# Application_Board.net
KiCad netlist of a schematic drawn in EAGLE
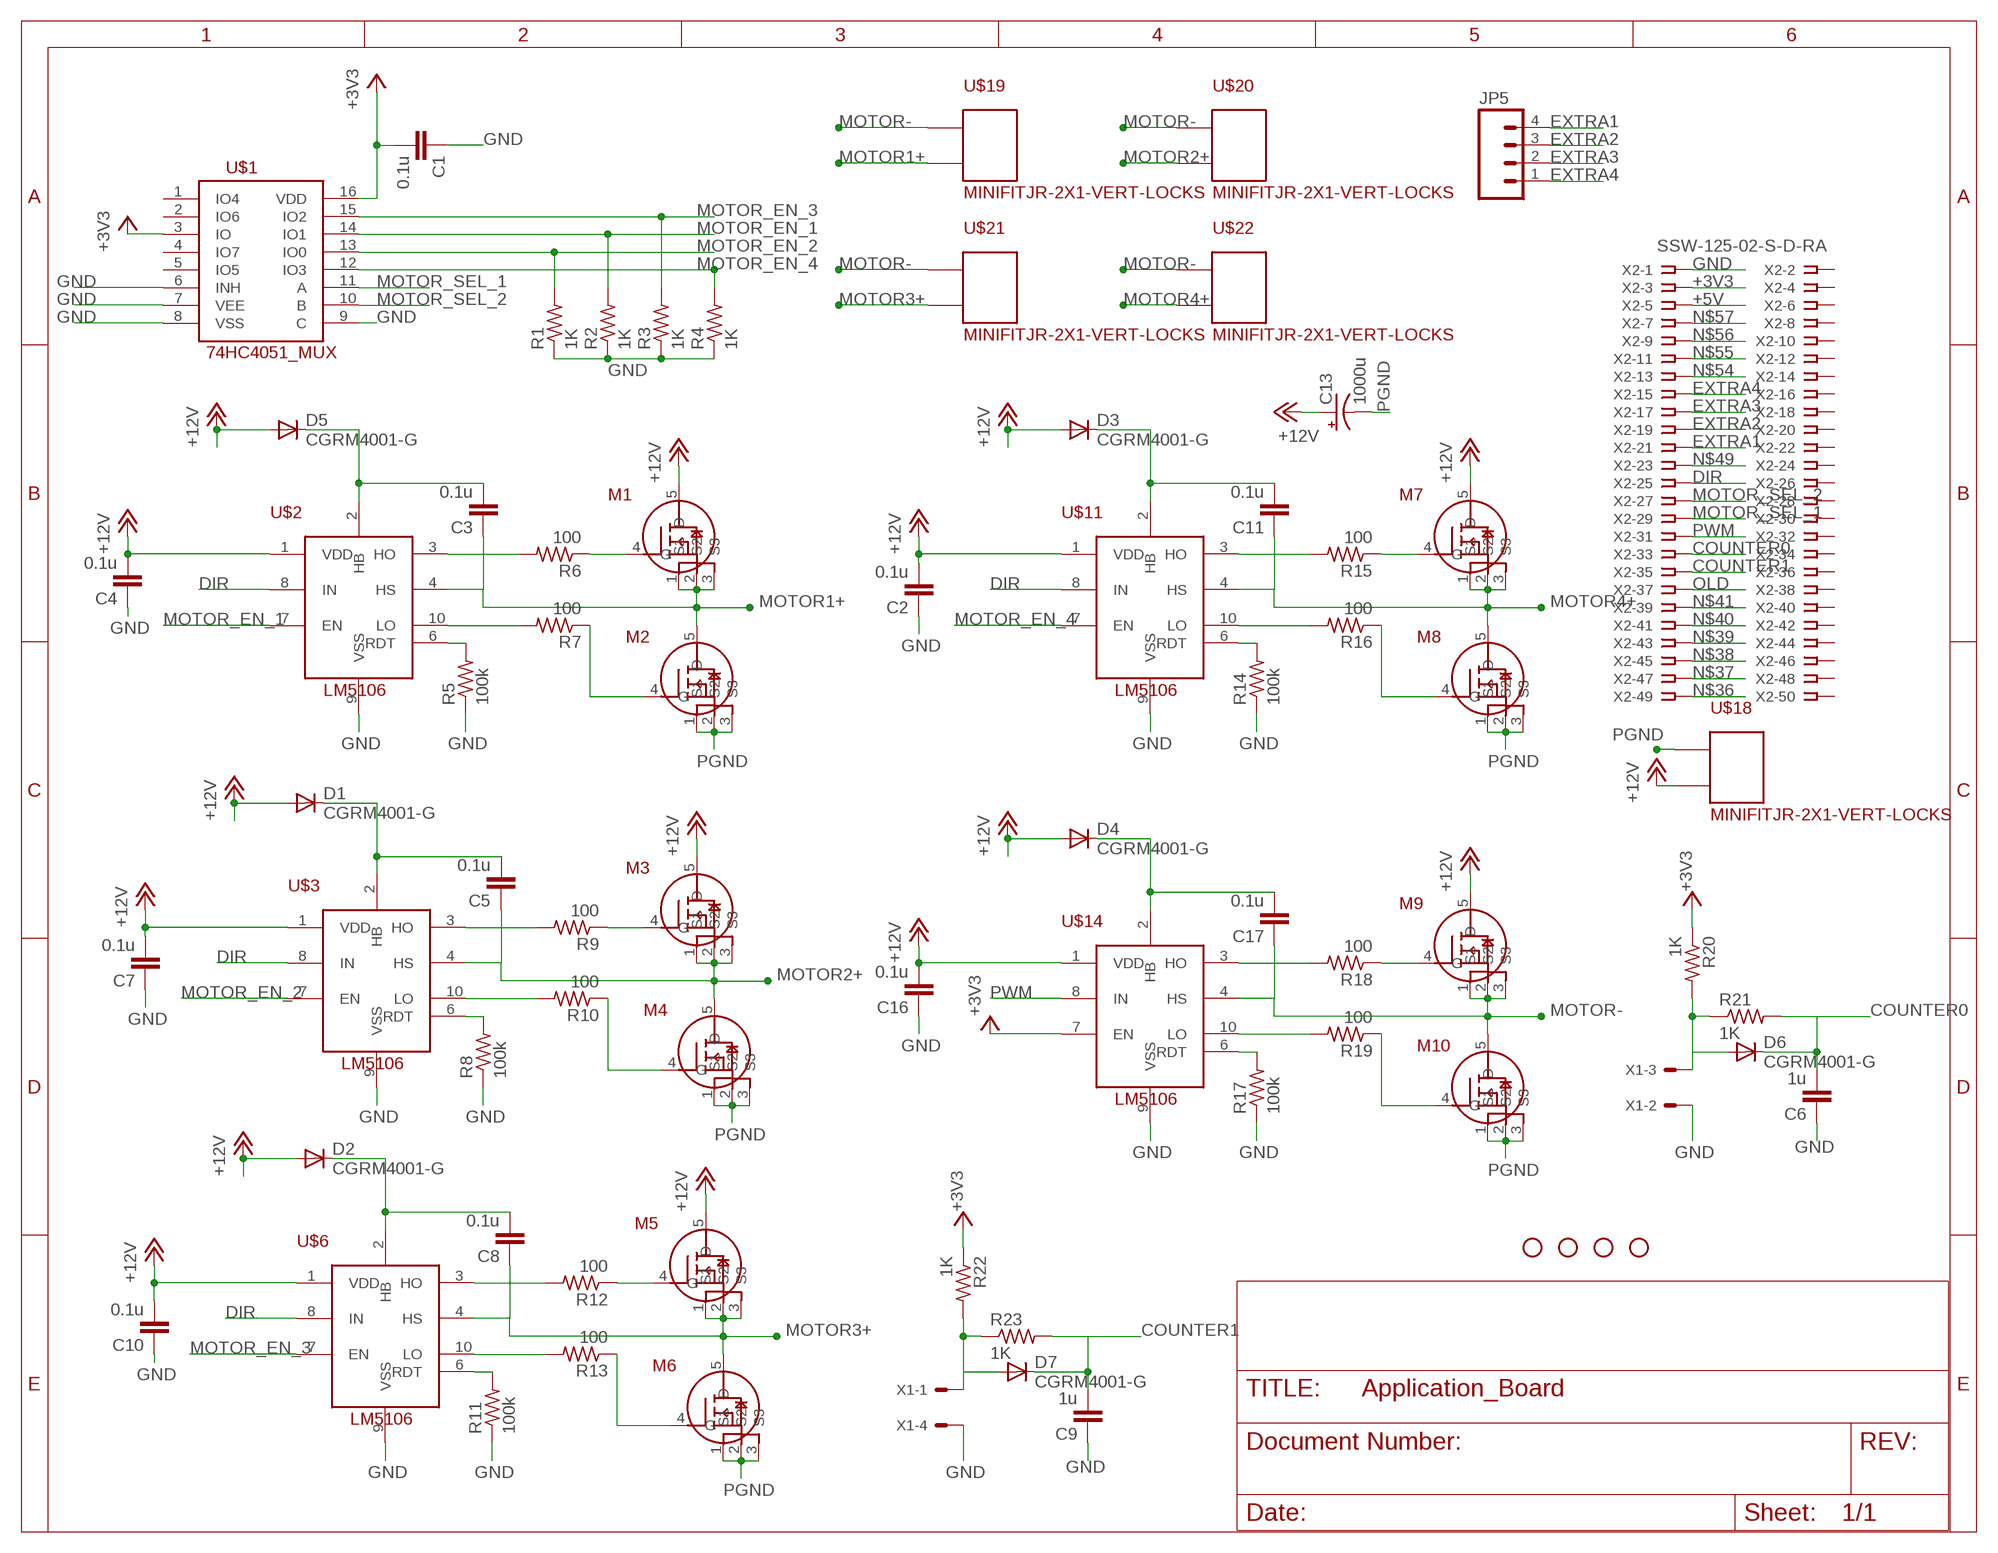
[diagram p0: schematic, sheet 1]

(export (version "E")
  (design (tool "Eeschema 10.0.6"))
  (components
    (comp (ref "C1")
      (value "0.1u")
      (footprint "eagle-import:0805")
      (libsource (lib "eagle-import") (part "CAP0805"))
    )
    (comp (ref "C2")
      (value "0.1u")
      (footprint "eagle-import:0805")
      (libsource (lib "eagle-import") (part "CAP0805"))
    )
    (comp (ref "C3")
      (value "0.1u")
      (footprint "eagle-import:0805")
      (libsource (lib "eagle-import") (part "CAP0805"))
    )
    (comp (ref "C4")
      (value "0.1u")
      (footprint "eagle-import:0805")
      (libsource (lib "eagle-import") (part "CAP0805"))
    )
    (comp (ref "C5")
      (value "0.1u")
      (footprint "eagle-import:0805")
      (libsource (lib "eagle-import") (part "CAP0805"))
    )
    (comp (ref "C6")
      (value "1u")
      (footprint "eagle-import:0805")
      (libsource (lib "eagle-import") (part "CAP0805"))
    )
    (comp (ref "C7")
      (value "0.1u")
      (footprint "eagle-import:0805")
      (libsource (lib "eagle-import") (part "CAP0805"))
    )
    (comp (ref "C8")
      (value "0.1u")
      (footprint "eagle-import:0805")
      (libsource (lib "eagle-import") (part "CAP0805"))
    )
    (comp (ref "C9")
      (value "1u")
      (footprint "eagle-import:0805")
      (libsource (lib "eagle-import") (part "CAP0805"))
    )
    (comp (ref "C10")
      (value "0.1u")
      (footprint "eagle-import:0805")
      (libsource (lib "eagle-import") (part "CAP0805"))
    )
    (comp (ref "C11")
      (value "0.1u")
      (footprint "eagle-import:0805")
      (libsource (lib "eagle-import") (part "CAP0805"))
    )
    (comp (ref "C13")
      (value "1000u")
      (footprint "eagle-import:UD-18X19,1_NICHICON")
      (libsource (lib "eagle-import") (part "CPOL-US"))
    )
    (comp (ref "C16")
      (value "0.1u")
      (footprint "eagle-import:0805")
      (libsource (lib "eagle-import") (part "CAP0805"))
    )
    (comp (ref "C17")
      (value "0.1u")
      (footprint "eagle-import:0805")
      (libsource (lib "eagle-import") (part "CAP0805"))
    )
    (comp (ref "D1")
      (value "CGRM4001-G")
      (footprint "eagle-import:SOD-123_MINI-SMA")
      (libsource (lib "eagle-import") (part "CGRM400-G1"))
    )
    (comp (ref "D2")
      (value "CGRM4001-G")
      (footprint "eagle-import:SOD-123_MINI-SMA")
      (libsource (lib "eagle-import") (part "CGRM400-G1"))
    )
    (comp (ref "D3")
      (value "CGRM4001-G")
      (footprint "eagle-import:SOD-123_MINI-SMA")
      (libsource (lib "eagle-import") (part "CGRM400-G1"))
    )
    (comp (ref "D4")
      (value "CGRM4001-G")
      (footprint "eagle-import:SOD-123_MINI-SMA")
      (libsource (lib "eagle-import") (part "CGRM400-G1"))
    )
    (comp (ref "D5")
      (value "CGRM4001-G")
      (footprint "eagle-import:SOD-123_MINI-SMA")
      (libsource (lib "eagle-import") (part "CGRM400-G1"))
    )
    (comp (ref "D6")
      (value "CGRM4001-G")
      (footprint "eagle-import:SOD-123_MINI-SMA")
      (libsource (lib "eagle-import") (part "CGRM400-G1"))
    )
    (comp (ref "D7")
      (value "CGRM4001-G")
      (footprint "eagle-import:SOD-123_MINI-SMA")
      (libsource (lib "eagle-import") (part "CGRM400-G1"))
    )
    (comp (ref "JP1")
      (value "STAND-OFF")
      (footprint "eagle-import:STAND-OFF")
      (libsource (lib "eagle-import") (part "STAND-OFF"))
    )
    (comp (ref "JP2")
      (value "STAND-OFF")
      (footprint "eagle-import:STAND-OFF")
      (libsource (lib "eagle-import") (part "STAND-OFF"))
    )
    (comp (ref "JP3")
      (value "STAND-OFF")
      (footprint "eagle-import:STAND-OFF")
      (libsource (lib "eagle-import") (part "STAND-OFF"))
    )
    (comp (ref "JP4")
      (value "STAND-OFF")
      (footprint "eagle-import:STAND-OFF")
      (libsource (lib "eagle-import") (part "STAND-OFF"))
    )
    (comp (ref "JP5")
      (value "M041X04_NO_SILK")
      (footprint "eagle-import:1X04_NO_SILK")
      (libsource (lib "eagle-import") (part "M041X04_NO_SILK"))
    )
    (comp (ref "M1")
      (value "M")
      (footprint "eagle-import:TO127P600X120-5N")
      (libsource (lib "eagle-import") (part "PSMN2R0-30YL"))
    )
    (comp (ref "M2")
      (value "M")
      (footprint "eagle-import:TO127P600X120-5N")
      (libsource (lib "eagle-import") (part "PSMN2R0-30YL"))
    )
    (comp (ref "M3")
      (value "M")
      (footprint "eagle-import:TO127P600X120-5N")
      (libsource (lib "eagle-import") (part "PSMN2R0-30YL"))
    )
    (comp (ref "M4")
      (value "M")
      (footprint "eagle-import:TO127P600X120-5N")
      (libsource (lib "eagle-import") (part "PSMN2R0-30YL"))
    )
    (comp (ref "M5")
      (value "M")
      (footprint "eagle-import:TO127P600X120-5N")
      (libsource (lib "eagle-import") (part "PSMN2R0-30YL"))
    )
    (comp (ref "M6")
      (value "M")
      (footprint "eagle-import:TO127P600X120-5N")
      (libsource (lib "eagle-import") (part "PSMN2R0-30YL"))
    )
    (comp (ref "M7")
      (value "M")
      (footprint "eagle-import:TO127P600X120-5N")
      (libsource (lib "eagle-import") (part "PSMN2R0-30YL"))
    )
    (comp (ref "M8")
      (value "M")
      (footprint "eagle-import:TO127P600X120-5N")
      (libsource (lib "eagle-import") (part "PSMN2R0-30YL"))
    )
    (comp (ref "M9")
      (value "M")
      (footprint "eagle-import:TO127P600X120-5N")
      (libsource (lib "eagle-import") (part "PSMN2R0-30YL"))
    )
    (comp (ref "M10")
      (value "M")
      (footprint "eagle-import:TO127P600X120-5N")
      (libsource (lib "eagle-import") (part "PSMN2R0-30YL"))
    )
    (comp (ref "R1")
      (value "1K")
      (footprint "eagle-import:R0805")
      (libsource (lib "eagle-import") (part "R-US_R0805"))
    )
    (comp (ref "R2")
      (value "1K")
      (footprint "eagle-import:R0805")
      (libsource (lib "eagle-import") (part "R-US_R0805"))
    )
    (comp (ref "R3")
      (value "1K")
      (footprint "eagle-import:R0805")
      (libsource (lib "eagle-import") (part "R-US_R0805"))
    )
    (comp (ref "R4")
      (value "1K")
      (footprint "eagle-import:R0805")
      (libsource (lib "eagle-import") (part "R-US_R0805"))
    )
    (comp (ref "R5")
      (value "100k")
      (footprint "eagle-import:R0805")
      (libsource (lib "eagle-import") (part "R-US_R0805"))
    )
    (comp (ref "R6")
      (value "100")
      (footprint "eagle-import:R0805")
      (libsource (lib "eagle-import") (part "R-US_R0805"))
    )
    (comp (ref "R7")
      (value "100")
      (footprint "eagle-import:R0805")
      (libsource (lib "eagle-import") (part "R-US_R0805"))
    )
    (comp (ref "R8")
      (value "100k")
      (footprint "eagle-import:R0805")
      (libsource (lib "eagle-import") (part "R-US_R0805"))
    )
    (comp (ref "R9")
      (value "100")
      (footprint "eagle-import:R0805")
      (libsource (lib "eagle-import") (part "R-US_R0805"))
    )
    (comp (ref "R10")
      (value "100")
      (footprint "eagle-import:R0805")
      (libsource (lib "eagle-import") (part "R-US_R0805"))
    )
    (comp (ref "R11")
      (value "100k")
      (footprint "eagle-import:R0805")
      (libsource (lib "eagle-import") (part "R-US_R0805"))
    )
    (comp (ref "R12")
      (value "100")
      (footprint "eagle-import:R0805")
      (libsource (lib "eagle-import") (part "R-US_R0805"))
    )
    (comp (ref "R13")
      (value "100")
      (footprint "eagle-import:R0805")
      (libsource (lib "eagle-import") (part "R-US_R0805"))
    )
    (comp (ref "R14")
      (value "100k")
      (footprint "eagle-import:R0805")
      (libsource (lib "eagle-import") (part "R-US_R0805"))
    )
    (comp (ref "R15")
      (value "100")
      (footprint "eagle-import:R0805")
      (libsource (lib "eagle-import") (part "R-US_R0805"))
    )
    (comp (ref "R16")
      (value "100")
      (footprint "eagle-import:R0805")
      (libsource (lib "eagle-import") (part "R-US_R0805"))
    )
    (comp (ref "R17")
      (value "100k")
      (footprint "eagle-import:R0805")
      (libsource (lib "eagle-import") (part "R-US_R0805"))
    )
    (comp (ref "R18")
      (value "100")
      (footprint "eagle-import:R0805")
      (libsource (lib "eagle-import") (part "R-US_R0805"))
    )
    (comp (ref "R19")
      (value "100")
      (footprint "eagle-import:R0805")
      (libsource (lib "eagle-import") (part "R-US_R0805"))
    )
    (comp (ref "R20")
      (value "1K")
      (footprint "eagle-import:R0805")
      (libsource (lib "eagle-import") (part "R-US_R0805"))
    )
    (comp (ref "R21")
      (value "1K")
      (footprint "eagle-import:R0805")
      (libsource (lib "eagle-import") (part "R-US_R0805"))
    )
    (comp (ref "R22")
      (value "1K")
      (footprint "eagle-import:R0805")
      (libsource (lib "eagle-import") (part "R-US_R0805"))
    )
    (comp (ref "R23")
      (value "1K")
      (footprint "eagle-import:R0805")
      (libsource (lib "eagle-import") (part "R-US_R0805"))
    )
    (comp (ref "U$1")
      (value "74HC4051_MUX")
      (footprint "eagle-import:SO16")
      (libsource (lib "eagle-import") (part "74HC4051_MUX"))
    )
    (comp (ref "U$2")
      (value "LM5106MMSMD-MSOP")
      (footprint "eagle-import:10-MSOP")
      (libsource (lib "eagle-import") (part "LM5106MMSMD-MSOP"))
    )
    (comp (ref "U$3")
      (value "LM5106MMSMD-MSOP")
      (footprint "eagle-import:10-MSOP")
      (libsource (lib "eagle-import") (part "LM5106MMSMD-MSOP"))
    )
    (comp (ref "U$6")
      (value "LM5106MMSMD-MSOP")
      (footprint "eagle-import:10-MSOP")
      (libsource (lib "eagle-import") (part "LM5106MMSMD-MSOP"))
    )
    (comp (ref "U$11")
      (value "LM5106MMSMD-MSOP")
      (footprint "eagle-import:10-MSOP")
      (libsource (lib "eagle-import") (part "LM5106MMSMD-MSOP"))
    )
    (comp (ref "U$14")
      (value "LM5106MMSMD-MSOP")
      (footprint "eagle-import:10-MSOP")
      (libsource (lib "eagle-import") (part "LM5106MMSMD-MSOP"))
    )
    (comp (ref "U$18")
      (value "MINIFITJR-2X1-VERT-LOCKS")
      (footprint "eagle-import:5566-02A2")
      (libsource (lib "eagle-import") (part "MINIFITJR-2X1-VERT-LOCKS"))
    )
    (comp (ref "U$19")
      (value "MINIFITJR-2X1-VERT-LOCKS")
      (footprint "eagle-import:5566-02A2")
      (libsource (lib "eagle-import") (part "MINIFITJR-2X1-VERT-LOCKS"))
    )
    (comp (ref "U$20")
      (value "MINIFITJR-2X1-VERT-LOCKS")
      (footprint "eagle-import:5566-02A2")
      (libsource (lib "eagle-import") (part "MINIFITJR-2X1-VERT-LOCKS"))
    )
    (comp (ref "U$21")
      (value "MINIFITJR-2X1-VERT-LOCKS")
      (footprint "eagle-import:5566-02A2")
      (libsource (lib "eagle-import") (part "MINIFITJR-2X1-VERT-LOCKS"))
    )
    (comp (ref "U$22")
      (value "MINIFITJR-2X1-VERT-LOCKS")
      (footprint "eagle-import:5566-02A2")
      (libsource (lib "eagle-import") (part "MINIFITJR-2X1-VERT-LOCKS"))
    )
    (comp (ref "X1")
      (value "KK-156-4")
      (footprint "eagle-import:KK-156-4")
      (libsource (lib "eagle-import") (part "KK-156-4"))
    )
    (comp (ref "X2")
      (value "SSW-125-02-S-D-RA")
      (footprint "eagle-import:TSW-125-02-S-D-RA")
      (libsource (lib "eagle-import") (part "SSW-125-02-S-D-RA"))
    )
  )
  (nets
    (net (code "1") (name "+3V3") (class "Default")
      (node (ref "C1") (pin "2") (pinfunction "2_2") (pintype "passive"))
      (node (ref "R20") (pin "1") (pinfunction "1_1") (pintype "passive"))
      (node (ref "R22") (pin "1") (pinfunction "1_1") (pintype "passive"))
      (node (ref "U$1") (pin "16") (pinfunction "VDD_16") (pintype "bidirectional"))
      (node (ref "U$1") (pin "3") (pinfunction "IO_3") (pintype "bidirectional"))
      (node (ref "U$14") (pin "7") (pinfunction "EN_7") (pintype "bidirectional"))
      (node (ref "X2") (pin "3") (pinfunction "1_3") (pintype "passive"))
    )
    (net (code "2") (name "+12V") (class "Default")
      (node (ref "C10") (pin "2") (pinfunction "2_2") (pintype "passive"))
      (node (ref "C13") (pin "+") (pinfunction "+_+") (pintype "passive"))
      (node (ref "C16") (pin "2") (pinfunction "2_2") (pintype "passive"))
      (node (ref "C2") (pin "2") (pinfunction "2_2") (pintype "passive"))
      (node (ref "C4") (pin "2") (pinfunction "2_2") (pintype "passive"))
      (node (ref "C7") (pin "2") (pinfunction "2_2") (pintype "passive"))
      (node (ref "D1") (pin "A") (pinfunction "A_A") (pintype "passive"))
      (node (ref "D2") (pin "A") (pinfunction "A_A") (pintype "passive"))
      (node (ref "D3") (pin "A") (pinfunction "A_A") (pintype "passive"))
      (node (ref "D4") (pin "A") (pinfunction "A_A") (pintype "passive"))
      (node (ref "D5") (pin "A") (pinfunction "A_A") (pintype "passive"))
      (node (ref "M1") (pin "5") (pinfunction "D_5") (pintype "bidirectional"))
      (node (ref "M3") (pin "5") (pinfunction "D_5") (pintype "bidirectional"))
      (node (ref "M5") (pin "5") (pinfunction "D_5") (pintype "bidirectional"))
      (node (ref "M7") (pin "5") (pinfunction "D_5") (pintype "bidirectional"))
      (node (ref "M9") (pin "5") (pinfunction "D_5") (pintype "bidirectional"))
      (node (ref "U$11") (pin "1") (pinfunction "VDD_1") (pintype "bidirectional"))
      (node (ref "U$14") (pin "1") (pinfunction "VDD_1") (pintype "bidirectional"))
      (node (ref "U$18") (pin "P$2") (pinfunction "P$2_P$2") (pintype "bidirectional"))
      (node (ref "U$2") (pin "1") (pinfunction "VDD_1") (pintype "bidirectional"))
      (node (ref "U$3") (pin "1") (pinfunction "VDD_1") (pintype "bidirectional"))
      (node (ref "U$6") (pin "1") (pinfunction "VDD_1") (pintype "bidirectional"))
    )
    (net (code "3") (name "/+5V") (class "Default")
      (node (ref "X2") (pin "5") (pinfunction "1_5") (pintype "passive"))
    )
    (net (code "4") (name "/COUNTER0") (class "Default")
      (node (ref "C6") (pin "2") (pinfunction "2_2") (pintype "passive"))
      (node (ref "D6") (pin "C") (pinfunction "C_C") (pintype "passive"))
      (node (ref "R21") (pin "2") (pinfunction "2_2") (pintype "passive"))
      (node (ref "X2") (pin "33") (pinfunction "1_33") (pintype "passive"))
    )
    (net (code "5") (name "/COUNTER1") (class "Default")
      (node (ref "C9") (pin "2") (pinfunction "2_2") (pintype "passive"))
      (node (ref "D7") (pin "C") (pinfunction "C_C") (pintype "passive"))
      (node (ref "R23") (pin "2") (pinfunction "2_2") (pintype "passive"))
      (node (ref "X2") (pin "35") (pinfunction "1_35") (pintype "passive"))
    )
    (net (code "6") (name "/DIR") (class "Default")
      (node (ref "U$11") (pin "8") (pinfunction "IN_8") (pintype "bidirectional"))
      (node (ref "U$2") (pin "8") (pinfunction "IN_8") (pintype "bidirectional"))
      (node (ref "U$3") (pin "8") (pinfunction "IN_8") (pintype "bidirectional"))
      (node (ref "U$6") (pin "8") (pinfunction "IN_8") (pintype "bidirectional"))
      (node (ref "X2") (pin "25") (pinfunction "1_25") (pintype "passive"))
    )
    (net (code "7") (name "/EXTRA1") (class "Default")
      (node (ref "JP5") (pin "4") (pinfunction "4_4") (pintype "passive"))
      (node (ref "X2") (pin "21") (pinfunction "1_21") (pintype "passive"))
    )
    (net (code "8") (name "/EXTRA2") (class "Default")
      (node (ref "JP5") (pin "3") (pinfunction "3_3") (pintype "passive"))
      (node (ref "X2") (pin "19") (pinfunction "1_19") (pintype "passive"))
    )
    (net (code "9") (name "/EXTRA3") (class "Default")
      (node (ref "JP5") (pin "2") (pinfunction "2_2") (pintype "passive"))
      (node (ref "X2") (pin "17") (pinfunction "1_17") (pintype "passive"))
    )
    (net (code "10") (name "/EXTRA4") (class "Default")
      (node (ref "JP5") (pin "1") (pinfunction "1_1") (pintype "passive"))
      (node (ref "X2") (pin "15") (pinfunction "1_15") (pintype "passive"))
    )
    (net (code "11") (name "/GND") (class "Default")
      (node (ref "C1") (pin "1") (pinfunction "1_1") (pintype "passive"))
      (node (ref "C10") (pin "1") (pinfunction "1_1") (pintype "passive"))
      (node (ref "C16") (pin "1") (pinfunction "1_1") (pintype "passive"))
      (node (ref "C2") (pin "1") (pinfunction "1_1") (pintype "passive"))
      (node (ref "C4") (pin "1") (pinfunction "1_1") (pintype "passive"))
      (node (ref "C6") (pin "1") (pinfunction "1_1") (pintype "passive"))
      (node (ref "C7") (pin "1") (pinfunction "1_1") (pintype "passive"))
      (node (ref "C9") (pin "1") (pinfunction "1_1") (pintype "passive"))
      (node (ref "R1") (pin "1") (pinfunction "1_1") (pintype "passive"))
      (node (ref "R11") (pin "1") (pinfunction "1_1") (pintype "passive"))
      (node (ref "R14") (pin "1") (pinfunction "1_1") (pintype "passive"))
      (node (ref "R17") (pin "1") (pinfunction "1_1") (pintype "passive"))
      (node (ref "R2") (pin "1") (pinfunction "1_1") (pintype "passive"))
      (node (ref "R3") (pin "1") (pinfunction "1_1") (pintype "passive"))
      (node (ref "R4") (pin "1") (pinfunction "1_1") (pintype "passive"))
      (node (ref "R5") (pin "1") (pinfunction "1_1") (pintype "passive"))
      (node (ref "R8") (pin "1") (pinfunction "1_1") (pintype "passive"))
      (node (ref "U$1") (pin "6") (pinfunction "INH_6") (pintype "bidirectional"))
      (node (ref "U$1") (pin "7") (pinfunction "VEE_7") (pintype "bidirectional"))
      (node (ref "U$1") (pin "8") (pinfunction "VSS_8") (pintype "bidirectional"))
      (node (ref "U$1") (pin "9") (pinfunction "C_9") (pintype "bidirectional"))
      (node (ref "U$11") (pin "9") (pinfunction "VSS_9") (pintype "bidirectional"))
      (node (ref "U$14") (pin "9") (pinfunction "VSS_9") (pintype "bidirectional"))
      (node (ref "U$2") (pin "9") (pinfunction "VSS_9") (pintype "bidirectional"))
      (node (ref "U$3") (pin "9") (pinfunction "VSS_9") (pintype "bidirectional"))
      (node (ref "U$6") (pin "9") (pinfunction "VSS_9") (pintype "bidirectional"))
      (node (ref "X1") (pin "2") (pinfunction "S_2") (pintype "passive"))
      (node (ref "X1") (pin "4") (pinfunction "S_4") (pintype "passive"))
      (node (ref "X2") (pin "1") (pinfunction "1_1") (pintype "passive"))
    )
    (net (code "12") (name "/MOTOR-") (class "Default")
      (node (ref "C17") (pin "1") (pinfunction "1_1") (pintype "passive"))
      (node (ref "M10") (pin "5") (pinfunction "D_5") (pintype "bidirectional"))
      (node (ref "M9") (pin "1") (pinfunction "S1_1") (pintype "bidirectional"))
      (node (ref "M9") (pin "2") (pinfunction "S2_2") (pintype "bidirectional"))
      (node (ref "M9") (pin "3") (pinfunction "S3_3") (pintype "bidirectional"))
      (node (ref "U$14") (pin "4") (pinfunction "HS_4") (pintype "bidirectional"))
      (node (ref "U$19") (pin "P$1") (pinfunction "P$1_P$1") (pintype "bidirectional"))
      (node (ref "U$20") (pin "P$1") (pinfunction "P$1_P$1") (pintype "bidirectional"))
      (node (ref "U$21") (pin "P$1") (pinfunction "P$1_P$1") (pintype "bidirectional"))
      (node (ref "U$22") (pin "P$1") (pinfunction "P$1_P$1") (pintype "bidirectional"))
    )
    (net (code "13") (name "/MOTOR1+") (class "Default")
      (node (ref "C3") (pin "1") (pinfunction "1_1") (pintype "passive"))
      (node (ref "M1") (pin "1") (pinfunction "S1_1") (pintype "bidirectional"))
      (node (ref "M1") (pin "2") (pinfunction "S2_2") (pintype "bidirectional"))
      (node (ref "M1") (pin "3") (pinfunction "S3_3") (pintype "bidirectional"))
      (node (ref "M2") (pin "5") (pinfunction "D_5") (pintype "bidirectional"))
      (node (ref "U$19") (pin "P$2") (pinfunction "P$2_P$2") (pintype "bidirectional"))
      (node (ref "U$2") (pin "4") (pinfunction "HS_4") (pintype "bidirectional"))
    )
    (net (code "14") (name "/MOTOR2+") (class "Default")
      (node (ref "C5") (pin "1") (pinfunction "1_1") (pintype "passive"))
      (node (ref "M3") (pin "1") (pinfunction "S1_1") (pintype "bidirectional"))
      (node (ref "M3") (pin "2") (pinfunction "S2_2") (pintype "bidirectional"))
      (node (ref "M3") (pin "3") (pinfunction "S3_3") (pintype "bidirectional"))
      (node (ref "M4") (pin "5") (pinfunction "D_5") (pintype "bidirectional"))
      (node (ref "U$20") (pin "P$2") (pinfunction "P$2_P$2") (pintype "bidirectional"))
      (node (ref "U$3") (pin "4") (pinfunction "HS_4") (pintype "bidirectional"))
    )
    (net (code "15") (name "/MOTOR3+") (class "Default")
      (node (ref "C8") (pin "1") (pinfunction "1_1") (pintype "passive"))
      (node (ref "M5") (pin "1") (pinfunction "S1_1") (pintype "bidirectional"))
      (node (ref "M5") (pin "2") (pinfunction "S2_2") (pintype "bidirectional"))
      (node (ref "M5") (pin "3") (pinfunction "S3_3") (pintype "bidirectional"))
      (node (ref "M6") (pin "5") (pinfunction "D_5") (pintype "bidirectional"))
      (node (ref "U$21") (pin "P$2") (pinfunction "P$2_P$2") (pintype "bidirectional"))
      (node (ref "U$6") (pin "4") (pinfunction "HS_4") (pintype "bidirectional"))
    )
    (net (code "16") (name "/MOTOR4+") (class "Default")
      (node (ref "C11") (pin "1") (pinfunction "1_1") (pintype "passive"))
      (node (ref "M7") (pin "1") (pinfunction "S1_1") (pintype "bidirectional"))
      (node (ref "M7") (pin "2") (pinfunction "S2_2") (pintype "bidirectional"))
      (node (ref "M7") (pin "3") (pinfunction "S3_3") (pintype "bidirectional"))
      (node (ref "M8") (pin "5") (pinfunction "D_5") (pintype "bidirectional"))
      (node (ref "U$11") (pin "4") (pinfunction "HS_4") (pintype "bidirectional"))
      (node (ref "U$22") (pin "P$2") (pinfunction "P$2_P$2") (pintype "bidirectional"))
    )
    (net (code "17") (name "/MOTOR_EN_1") (class "Default")
      (node (ref "R2") (pin "2") (pinfunction "2_2") (pintype "passive"))
      (node (ref "U$1") (pin "14") (pinfunction "IO1_14") (pintype "bidirectional"))
      (node (ref "U$2") (pin "7") (pinfunction "EN_7") (pintype "bidirectional"))
    )
    (net (code "18") (name "/MOTOR_EN_2") (class "Default")
      (node (ref "R1") (pin "2") (pinfunction "2_2") (pintype "passive"))
      (node (ref "U$1") (pin "13") (pinfunction "IO0_13") (pintype "bidirectional"))
      (node (ref "U$3") (pin "7") (pinfunction "EN_7") (pintype "bidirectional"))
    )
    (net (code "19") (name "/MOTOR_EN_3") (class "Default")
      (node (ref "R3") (pin "2") (pinfunction "2_2") (pintype "passive"))
      (node (ref "U$1") (pin "15") (pinfunction "IO2_15") (pintype "bidirectional"))
      (node (ref "U$6") (pin "7") (pinfunction "EN_7") (pintype "bidirectional"))
    )
    (net (code "20") (name "/MOTOR_EN_4") (class "Default")
      (node (ref "R4") (pin "2") (pinfunction "2_2") (pintype "passive"))
      (node (ref "U$1") (pin "12") (pinfunction "IO3_12") (pintype "bidirectional"))
      (node (ref "U$11") (pin "7") (pinfunction "EN_7") (pintype "bidirectional"))
    )
    (net (code "21") (name "/MOTOR_SEL_1") (class "Default")
      (node (ref "U$1") (pin "11") (pinfunction "A_11") (pintype "bidirectional"))
      (node (ref "X2") (pin "29") (pinfunction "1_29") (pintype "passive"))
    )
    (net (code "22") (name "/MOTOR_SEL_2") (class "Default")
      (node (ref "U$1") (pin "10") (pinfunction "B_10") (pintype "bidirectional"))
      (node (ref "X2") (pin "27") (pinfunction "1_27") (pintype "passive"))
    )
    (net (code "23") (name "/N$36") (class "Default")
      (node (ref "X2") (pin "49") (pinfunction "1_49") (pintype "passive"))
    )
    (net (code "24") (name "/N$37") (class "Default")
      (node (ref "X2") (pin "47") (pinfunction "1_47") (pintype "passive"))
    )
    (net (code "25") (name "/N$38") (class "Default")
      (node (ref "X2") (pin "45") (pinfunction "1_45") (pintype "passive"))
    )
    (net (code "26") (name "/N$39") (class "Default")
      (node (ref "X2") (pin "43") (pinfunction "1_43") (pintype "passive"))
    )
    (net (code "27") (name "/N$40") (class "Default")
      (node (ref "X2") (pin "41") (pinfunction "1_41") (pintype "passive"))
    )
    (net (code "28") (name "/N$41") (class "Default")
      (node (ref "X2") (pin "39") (pinfunction "1_39") (pintype "passive"))
    )
    (net (code "29") (name "/N$49") (class "Default")
      (node (ref "X2") (pin "23") (pinfunction "1_23") (pintype "passive"))
    )
    (net (code "30") (name "/N$54") (class "Default")
      (node (ref "X2") (pin "13") (pinfunction "1_13") (pintype "passive"))
    )
    (net (code "31") (name "/N$55") (class "Default")
      (node (ref "X2") (pin "11") (pinfunction "1_11") (pintype "passive"))
    )
    (net (code "32") (name "/N$56") (class "Default")
      (node (ref "X2") (pin "9") (pinfunction "1_9") (pintype "passive"))
    )
    (net (code "33") (name "/N$57") (class "Default")
      (node (ref "X2") (pin "7") (pinfunction "1_7") (pintype "passive"))
    )
    (net (code "34") (name "/OLD") (class "Default")
      (node (ref "X2") (pin "37") (pinfunction "1_37") (pintype "passive"))
    )
    (net (code "35") (name "/PGND") (class "Default")
      (node (ref "C13") (pin "-") (pinfunction "-_-") (pintype "passive"))
      (node (ref "M10") (pin "1") (pinfunction "S1_1") (pintype "bidirectional"))
      (node (ref "M10") (pin "2") (pinfunction "S2_2") (pintype "bidirectional"))
      (node (ref "M10") (pin "3") (pinfunction "S3_3") (pintype "bidirectional"))
      (node (ref "M2") (pin "1") (pinfunction "S1_1") (pintype "bidirectional"))
      (node (ref "M2") (pin "2") (pinfunction "S2_2") (pintype "bidirectional"))
      (node (ref "M2") (pin "3") (pinfunction "S3_3") (pintype "bidirectional"))
      (node (ref "M4") (pin "1") (pinfunction "S1_1") (pintype "bidirectional"))
      (node (ref "M4") (pin "2") (pinfunction "S2_2") (pintype "bidirectional"))
      (node (ref "M4") (pin "3") (pinfunction "S3_3") (pintype "bidirectional"))
      (node (ref "M6") (pin "1") (pinfunction "S1_1") (pintype "bidirectional"))
      (node (ref "M6") (pin "2") (pinfunction "S2_2") (pintype "bidirectional"))
      (node (ref "M6") (pin "3") (pinfunction "S3_3") (pintype "bidirectional"))
      (node (ref "M8") (pin "1") (pinfunction "S1_1") (pintype "bidirectional"))
      (node (ref "M8") (pin "2") (pinfunction "S2_2") (pintype "bidirectional"))
      (node (ref "M8") (pin "3") (pinfunction "S3_3") (pintype "bidirectional"))
      (node (ref "U$18") (pin "P$1") (pinfunction "P$1_P$1") (pintype "bidirectional"))
    )
    (net (code "36") (name "/PWM") (class "Default")
      (node (ref "U$14") (pin "8") (pinfunction "IN_8") (pintype "bidirectional"))
      (node (ref "X2") (pin "31") (pinfunction "1_31") (pintype "passive"))
    )
    (net (code "37") (name "Net-(M1-G)") (class "Default")
      (node (ref "M1") (pin "4") (pinfunction "G_4") (pintype "bidirectional"))
      (node (ref "R6") (pin "1") (pinfunction "1_1") (pintype "passive"))
    )
    (net (code "38") (name "Net-(M2-G)") (class "Default")
      (node (ref "M2") (pin "4") (pinfunction "G_4") (pintype "bidirectional"))
      (node (ref "R7") (pin "1") (pinfunction "1_1") (pintype "passive"))
    )
    (net (code "39") (name "Net-(M3-G)") (class "Default")
      (node (ref "M3") (pin "4") (pinfunction "G_4") (pintype "bidirectional"))
      (node (ref "R9") (pin "1") (pinfunction "1_1") (pintype "passive"))
    )
    (net (code "40") (name "Net-(M4-G)") (class "Default")
      (node (ref "M4") (pin "4") (pinfunction "G_4") (pintype "bidirectional"))
      (node (ref "R10") (pin "1") (pinfunction "1_1") (pintype "passive"))
    )
    (net (code "41") (name "Net-(M5-G)") (class "Default")
      (node (ref "M5") (pin "4") (pinfunction "G_4") (pintype "bidirectional"))
      (node (ref "R12") (pin "1") (pinfunction "1_1") (pintype "passive"))
    )
    (net (code "42") (name "Net-(M6-G)") (class "Default")
      (node (ref "M6") (pin "4") (pinfunction "G_4") (pintype "bidirectional"))
      (node (ref "R13") (pin "1") (pinfunction "1_1") (pintype "passive"))
    )
    (net (code "43") (name "Net-(M7-G)") (class "Default")
      (node (ref "M7") (pin "4") (pinfunction "G_4") (pintype "bidirectional"))
      (node (ref "R15") (pin "1") (pinfunction "1_1") (pintype "passive"))
    )
    (net (code "44") (name "Net-(M8-G)") (class "Default")
      (node (ref "M8") (pin "4") (pinfunction "G_4") (pintype "bidirectional"))
      (node (ref "R16") (pin "1") (pinfunction "1_1") (pintype "passive"))
    )
    (net (code "45") (name "Net-(M9-G)") (class "Default")
      (node (ref "M9") (pin "4") (pinfunction "G_4") (pintype "bidirectional"))
      (node (ref "R18") (pin "1") (pinfunction "1_1") (pintype "passive"))
    )
    (net (code "46") (name "Net-(M10-G)") (class "Default")
      (node (ref "M10") (pin "4") (pinfunction "G_4") (pintype "bidirectional"))
      (node (ref "R19") (pin "1") (pinfunction "1_1") (pintype "passive"))
    )
    (net (code "47") (name "Net-(U$2-HB)") (class "Default")
      (node (ref "C3") (pin "2") (pinfunction "2_2") (pintype "passive"))
      (node (ref "D5") (pin "C") (pinfunction "C_C") (pintype "passive"))
      (node (ref "U$2") (pin "2") (pinfunction "HB_2") (pintype "bidirectional"))
    )
    (net (code "48") (name "Net-(U$2-HO)") (class "Default")
      (node (ref "R6") (pin "2") (pinfunction "2_2") (pintype "passive"))
      (node (ref "U$2") (pin "3") (pinfunction "HO_3") (pintype "bidirectional"))
    )
    (net (code "49") (name "Net-(U$2-LO)") (class "Default")
      (node (ref "R7") (pin "2") (pinfunction "2_2") (pintype "passive"))
      (node (ref "U$2") (pin "10") (pinfunction "LO_10") (pintype "bidirectional"))
    )
    (net (code "50") (name "Net-(U$2-RDT)") (class "Default")
      (node (ref "R5") (pin "2") (pinfunction "2_2") (pintype "passive"))
      (node (ref "U$2") (pin "6") (pinfunction "RDT_6") (pintype "bidirectional"))
    )
    (net (code "51") (name "Net-(U$3-HB)") (class "Default")
      (node (ref "C5") (pin "2") (pinfunction "2_2") (pintype "passive"))
      (node (ref "D1") (pin "C") (pinfunction "C_C") (pintype "passive"))
      (node (ref "U$3") (pin "2") (pinfunction "HB_2") (pintype "bidirectional"))
    )
    (net (code "52") (name "Net-(U$3-HO)") (class "Default")
      (node (ref "R9") (pin "2") (pinfunction "2_2") (pintype "passive"))
      (node (ref "U$3") (pin "3") (pinfunction "HO_3") (pintype "bidirectional"))
    )
    (net (code "53") (name "Net-(U$3-LO)") (class "Default")
      (node (ref "R10") (pin "2") (pinfunction "2_2") (pintype "passive"))
      (node (ref "U$3") (pin "10") (pinfunction "LO_10") (pintype "bidirectional"))
    )
    (net (code "54") (name "Net-(U$3-RDT)") (class "Default")
      (node (ref "R8") (pin "2") (pinfunction "2_2") (pintype "passive"))
      (node (ref "U$3") (pin "6") (pinfunction "RDT_6") (pintype "bidirectional"))
    )
    (net (code "55") (name "Net-(U$6-HB)") (class "Default")
      (node (ref "C8") (pin "2") (pinfunction "2_2") (pintype "passive"))
      (node (ref "D2") (pin "C") (pinfunction "C_C") (pintype "passive"))
      (node (ref "U$6") (pin "2") (pinfunction "HB_2") (pintype "bidirectional"))
    )
    (net (code "56") (name "Net-(U$6-HO)") (class "Default")
      (node (ref "R12") (pin "2") (pinfunction "2_2") (pintype "passive"))
      (node (ref "U$6") (pin "3") (pinfunction "HO_3") (pintype "bidirectional"))
    )
    (net (code "57") (name "Net-(U$6-LO)") (class "Default")
      (node (ref "R13") (pin "2") (pinfunction "2_2") (pintype "passive"))
      (node (ref "U$6") (pin "10") (pinfunction "LO_10") (pintype "bidirectional"))
    )
    (net (code "58") (name "Net-(U$6-RDT)") (class "Default")
      (node (ref "R11") (pin "2") (pinfunction "2_2") (pintype "passive"))
      (node (ref "U$6") (pin "6") (pinfunction "RDT_6") (pintype "bidirectional"))
    )
    (net (code "59") (name "Net-(U$11-HB)") (class "Default")
      (node (ref "C11") (pin "2") (pinfunction "2_2") (pintype "passive"))
      (node (ref "D3") (pin "C") (pinfunction "C_C") (pintype "passive"))
      (node (ref "U$11") (pin "2") (pinfunction "HB_2") (pintype "bidirectional"))
    )
    (net (code "60") (name "Net-(U$11-HO)") (class "Default")
      (node (ref "R15") (pin "2") (pinfunction "2_2") (pintype "passive"))
      (node (ref "U$11") (pin "3") (pinfunction "HO_3") (pintype "bidirectional"))
    )
    (net (code "61") (name "Net-(U$11-LO)") (class "Default")
      (node (ref "R16") (pin "2") (pinfunction "2_2") (pintype "passive"))
      (node (ref "U$11") (pin "10") (pinfunction "LO_10") (pintype "bidirectional"))
    )
    (net (code "62") (name "Net-(U$11-RDT)") (class "Default")
      (node (ref "R14") (pin "2") (pinfunction "2_2") (pintype "passive"))
      (node (ref "U$11") (pin "6") (pinfunction "RDT_6") (pintype "bidirectional"))
    )
    (net (code "63") (name "Net-(U$14-HB)") (class "Default")
      (node (ref "C17") (pin "2") (pinfunction "2_2") (pintype "passive"))
      (node (ref "D4") (pin "C") (pinfunction "C_C") (pintype "passive"))
      (node (ref "U$14") (pin "2") (pinfunction "HB_2") (pintype "bidirectional"))
    )
    (net (code "64") (name "Net-(U$14-HO)") (class "Default")
      (node (ref "R18") (pin "2") (pinfunction "2_2") (pintype "passive"))
      (node (ref "U$14") (pin "3") (pinfunction "HO_3") (pintype "bidirectional"))
    )
    (net (code "65") (name "Net-(U$14-LO)") (class "Default")
      (node (ref "R19") (pin "2") (pinfunction "2_2") (pintype "passive"))
      (node (ref "U$14") (pin "10") (pinfunction "LO_10") (pintype "bidirectional"))
    )
    (net (code "66") (name "Net-(U$14-RDT)") (class "Default")
      (node (ref "R17") (pin "2") (pinfunction "2_2") (pintype "passive"))
      (node (ref "U$14") (pin "6") (pinfunction "RDT_6") (pintype "bidirectional"))
    )
    (net (code "67") (name "Net-(X1A-S)") (class "Default")
      (node (ref "D7") (pin "A") (pinfunction "A_A") (pintype "passive"))
      (node (ref "R22") (pin "2") (pinfunction "2_2") (pintype "passive"))
      (node (ref "R23") (pin "1") (pinfunction "1_1") (pintype "passive"))
      (node (ref "X1") (pin "1") (pinfunction "S_1") (pintype "passive"))
    )
    (net (code "68") (name "Net-(X1C-S)") (class "Default")
      (node (ref "D6") (pin "A") (pinfunction "A_A") (pintype "passive"))
      (node (ref "R20") (pin "2") (pinfunction "2_2") (pintype "passive"))
      (node (ref "R21") (pin "1") (pinfunction "1_1") (pintype "passive"))
      (node (ref "X1") (pin "3") (pinfunction "S_3") (pintype "passive"))
    )
    (net (code "69") (name "unconnected-(U$1-IO4-Pad1)") (class "Default")
      (node (ref "U$1") (pin "1") (pinfunction "IO4_1") (pintype "bidirectional"))
    )
    (net (code "70") (name "unconnected-(U$1-IO5-Pad5)") (class "Default")
      (node (ref "U$1") (pin "5") (pinfunction "IO5_5") (pintype "bidirectional"))
    )
    (net (code "71") (name "unconnected-(U$1-IO6-Pad2)") (class "Default")
      (node (ref "U$1") (pin "2") (pinfunction "IO6_2") (pintype "bidirectional"))
    )
    (net (code "72") (name "unconnected-(U$1-IO7-Pad4)") (class "Default")
      (node (ref "U$1") (pin "4") (pinfunction "IO7_4") (pintype "bidirectional"))
    )
    (net (code "73") (name "unconnected-(X2AB-1-Pad34)") (class "Default")
      (node (ref "X2") (pin "34") (pinfunction "1_34") (pintype "passive"))
    )
    (net (code "74") (name "unconnected-(X2AD-1-Pad36)") (class "Default")
      (node (ref "X2") (pin "36") (pinfunction "1_36") (pintype "passive"))
    )
    (net (code "75") (name "unconnected-(X2AF-1-Pad38)") (class "Default")
      (node (ref "X2") (pin "38") (pinfunction "1_38") (pintype "passive"))
    )
    (net (code "76") (name "unconnected-(X2AH-1-Pad4)") (class "Default")
      (node (ref "X2") (pin "4") (pinfunction "1_4") (pintype "passive"))
    )
    (net (code "77") (name "unconnected-(X2AI-1-Pad40)") (class "Default")
      (node (ref "X2") (pin "40") (pinfunction "1_40") (pintype "passive"))
    )
    (net (code "78") (name "unconnected-(X2AK-1-Pad42)") (class "Default")
      (node (ref "X2") (pin "42") (pinfunction "1_42") (pintype "passive"))
    )
    (net (code "79") (name "unconnected-(X2AM-1-Pad44)") (class "Default")
      (node (ref "X2") (pin "44") (pinfunction "1_44") (pintype "passive"))
    )
    (net (code "80") (name "unconnected-(X2AO-1-Pad46)") (class "Default")
      (node (ref "X2") (pin "46") (pinfunction "1_46") (pintype "passive"))
    )
    (net (code "81") (name "unconnected-(X2AQ-1-Pad48)") (class "Default")
      (node (ref "X2") (pin "48") (pinfunction "1_48") (pintype "passive"))
    )
    (net (code "82") (name "unconnected-(X2AT-1-Pad50)") (class "Default")
      (node (ref "X2") (pin "50") (pinfunction "1_50") (pintype "passive"))
    )
    (net (code "83") (name "unconnected-(X2AU-1-Pad6)") (class "Default")
      (node (ref "X2") (pin "6") (pinfunction "1_6") (pintype "passive"))
    )
    (net (code "84") (name "unconnected-(X2AW-1-Pad8)") (class "Default")
      (node (ref "X2") (pin "8") (pinfunction "1_8") (pintype "passive"))
    )
    (net (code "85") (name "unconnected-(X2B-1-Pad10)") (class "Default")
      (node (ref "X2") (pin "10") (pinfunction "1_10") (pintype "passive"))
    )
    (net (code "86") (name "unconnected-(X2D-1-Pad12)") (class "Default")
      (node (ref "X2") (pin "12") (pinfunction "1_12") (pintype "passive"))
    )
    (net (code "87") (name "unconnected-(X2F-1-Pad14)") (class "Default")
      (node (ref "X2") (pin "14") (pinfunction "1_14") (pintype "passive"))
    )
    (net (code "88") (name "unconnected-(X2H-1-Pad16)") (class "Default")
      (node (ref "X2") (pin "16") (pinfunction "1_16") (pintype "passive"))
    )
    (net (code "89") (name "unconnected-(X2J-1-Pad18)") (class "Default")
      (node (ref "X2") (pin "18") (pinfunction "1_18") (pintype "passive"))
    )
    (net (code "90") (name "unconnected-(X2L-1-Pad2)") (class "Default")
      (node (ref "X2") (pin "2") (pinfunction "1_2") (pintype "passive"))
    )
    (net (code "91") (name "unconnected-(X2M-1-Pad20)") (class "Default")
      (node (ref "X2") (pin "20") (pinfunction "1_20") (pintype "passive"))
    )
    (net (code "92") (name "unconnected-(X2O-1-Pad22)") (class "Default")
      (node (ref "X2") (pin "22") (pinfunction "1_22") (pintype "passive"))
    )
    (net (code "93") (name "unconnected-(X2Q-1-Pad24)") (class "Default")
      (node (ref "X2") (pin "24") (pinfunction "1_24") (pintype "passive"))
    )
    (net (code "94") (name "unconnected-(X2S-1-Pad26)") (class "Default")
      (node (ref "X2") (pin "26") (pinfunction "1_26") (pintype "passive"))
    )
    (net (code "95") (name "unconnected-(X2U-1-Pad28)") (class "Default")
      (node (ref "X2") (pin "28") (pinfunction "1_28") (pintype "passive"))
    )
    (net (code "96") (name "unconnected-(X2X-1-Pad30)") (class "Default")
      (node (ref "X2") (pin "30") (pinfunction "1_30") (pintype "passive"))
    )
    (net (code "97") (name "unconnected-(X2Z-1-Pad32)") (class "Default")
      (node (ref "X2") (pin "32") (pinfunction "1_32") (pintype "passive"))
    )
  )
)
